# Pop.net
KiCad netlist of a schematic drawn in Altium Designer
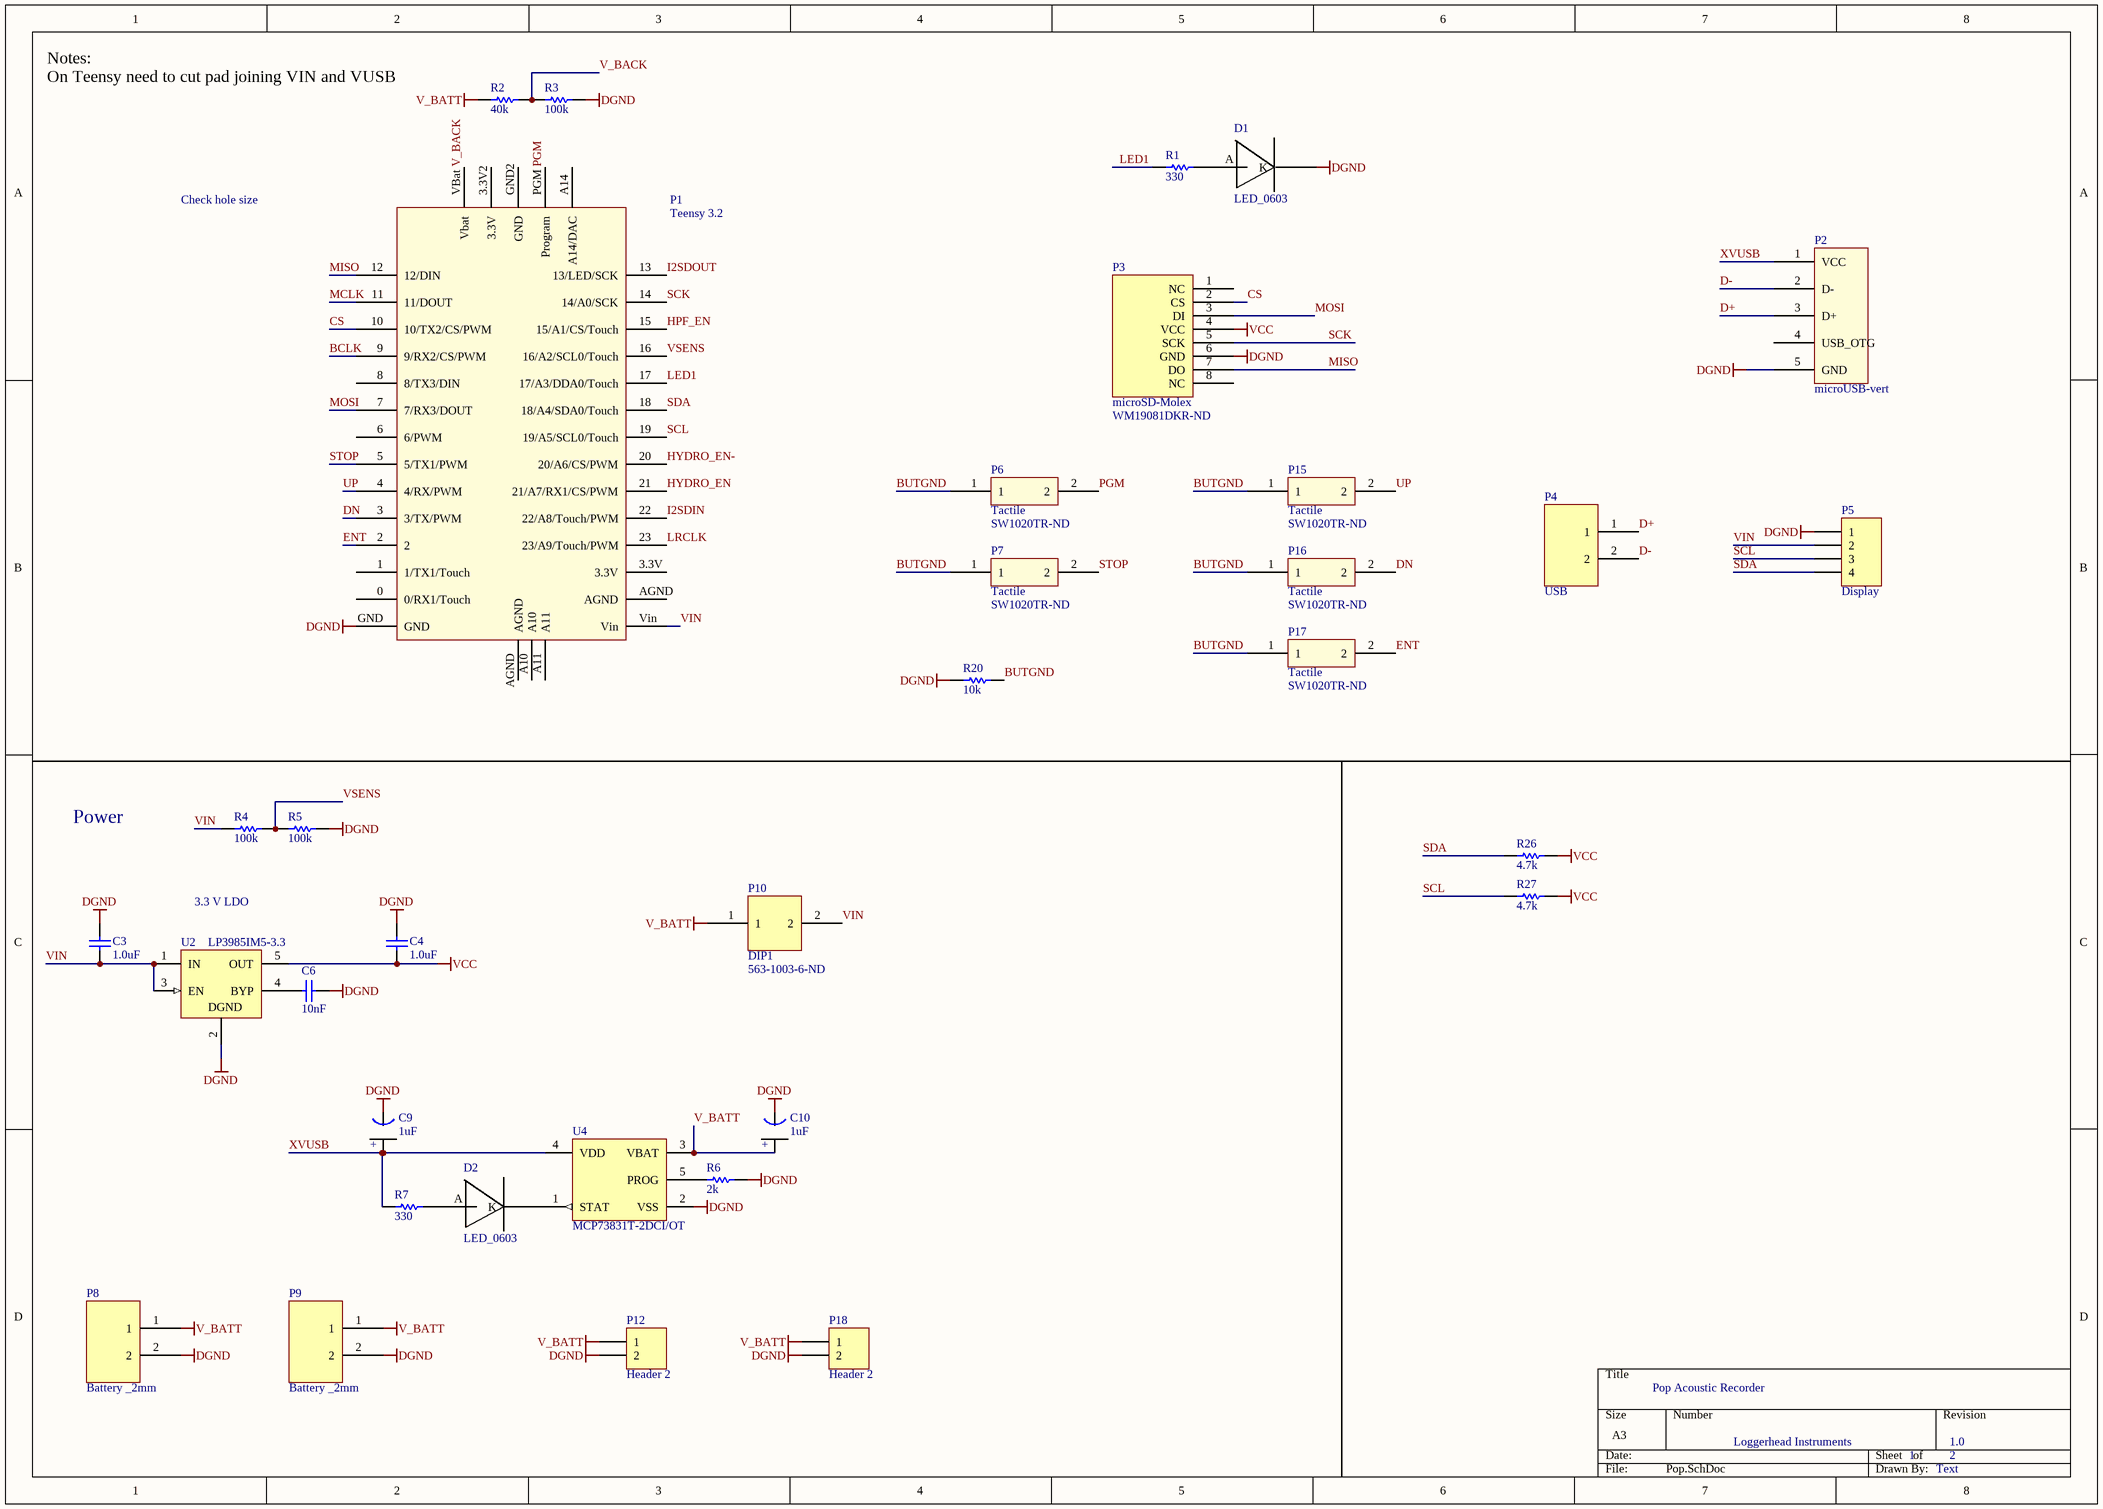
[diagram p0: Pop.SchDoc]

(export (version "E")
  (design (tool "Eeschema 10.0.6"))
  (components
    (comp (ref "C3")
      (value "1.0uF")
      (footprint "0402")
      (description "Ceramic Chip Capacitor - Standard")
      (fields (field (name "PUBLISHER") "Altium Limited"))
      (libsource (lib "KEMET Chip Capacitor") (part "C0402"))
    )
    (comp (ref "C4")
      (value "1.0uF")
      (footprint "0402")
      (description "Ceramic Chip Capacitor - Standard")
      (fields (field (name "PUBLISHER") "Altium Limited"))
      (libsource (lib "KEMET Chip Capacitor") (part "C0402"))
    )
    (comp (ref "C6")
      (value "10nF")
      (footprint "0402")
      (description "Ceramic Chip Capacitor - Standard")
      (fields (field (name "PUBLISHER") "Altium Limited"))
      (libsource (lib "KEMET Chip Capacitor") (part "C0402"))
    )
    (comp (ref "C9") (value "1uF") (footprint "Tant0805") (libsource (lib "Loggerhead") (part "Tant0805")))
    (comp (ref "C10") (value "1uF") (footprint "Tant0805") (libsource (lib "Loggerhead") (part "Tant0805")))
    (comp (ref "D1")
      (value "LED_0603")
      (footprint "Diode0603")
      (libsource (lib "Loggerhead") (part "LED_0603"))
    )
    (comp (ref "D2")
      (value "LED_0603")
      (footprint "Diode0603")
      (libsource (lib "Loggerhead") (part "LED_0603"))
    )
    (comp (ref "P1")
      (value "Teensy 3.2")
      (footprint "Teensy3.x")
      (libsource (lib "Teensy") (part "Teensy3.x"))
    )
    (comp (ref "P2")
      (value "microUSB-vert")
      (footprint "MICROUSB-VERT")
      (description "Molex 105133-0011")
      (libsource (lib "Loggerhead") (part "microUSB-vert"))
    )
    (comp (ref "P3")
      (value "microSD-Molex")
      (footprint "microSD_Molex_hinged")
      (fields (field (name "SUPPLIER PART NUMBER 1") "WM19081DKR-ND"))
      (libsource (lib "Loggerhead") (part "microSD_Molex_hinged"))
    )
    (comp (ref "P4")
      (value "USB")
      (footprint "HDR_2x1_2mm")
      (description "Charging Connector")
      (libsource (lib "Loggerhead") (part "HDR_2x1_2mm"))
    )
    (comp (ref "P5")
      (value "Display")
      (footprint "HDR1X4")
      (description "Header, 4-Pin")
      (fields (field (name "PUBLISHER") "Altium Limited"))
      (libsource (lib "Miscellaneous Connectors") (part "Header 4"))
    )
    (comp (ref "P6")
      (value "Tactile")
      (footprint "Tactile-B3U-1000")
      (fields (field (name "SUPPLIER PART NUMBER 1") "SW1020TR-ND"))
      (libsource (lib "Loggerhead") (part "Tactile_B3U-1000"))
    )
    (comp (ref "P7")
      (value "Tactile")
      (footprint "Tactile-B3U-1000")
      (fields (field (name "SUPPLIER PART NUMBER 1") "SW1020TR-ND"))
      (libsource (lib "Loggerhead") (part "Tactile_B3U-1000"))
    )
    (comp (ref "P8")
      (value "Battery _2mm")
      (footprint "HDR_2x1_2mm")
      (description "Charging Connector")
      (libsource (lib "Loggerhead") (part "HDR_2x1_2mm"))
    )
    (comp (ref "P9")
      (value "Battery _2mm")
      (footprint "HDR_2x1_2mm")
      (description "Charging Connector")
      (libsource (lib "Loggerhead") (part "HDR_2x1_2mm"))
    )
    (comp (ref "P10")
      (value "DIP1")
      (footprint "DIP1")
      (fields (field (name "SUPPLIER PART NUMBER 1") "563-1003-6-ND"))
      (libsource (lib "Loggerhead") (part "DIP1"))
    )
    (comp (ref "P12")
      (value "Header 2")
      (footprint "HDR1X2")
      (description "Header, 2-Pin")
      (fields (field (name "PUBLISHER") "Altium Limited"))
      (libsource (lib "Miscellaneous Connectors") (part "Header 2"))
    )
    (comp (ref "P15")
      (value "Tactile")
      (footprint "Tactile-B3U-1000")
      (fields (field (name "SUPPLIER PART NUMBER 1") "SW1020TR-ND"))
      (libsource (lib "Loggerhead") (part "Tactile_B3U-1000"))
    )
    (comp (ref "P16")
      (value "Tactile")
      (footprint "Tactile-B3U-1000")
      (fields (field (name "SUPPLIER PART NUMBER 1") "SW1020TR-ND"))
      (libsource (lib "Loggerhead") (part "Tactile_B3U-1000"))
    )
    (comp (ref "P17")
      (value "Tactile")
      (footprint "Tactile-B3U-1000")
      (fields (field (name "SUPPLIER PART NUMBER 1") "SW1020TR-ND"))
      (libsource (lib "Loggerhead") (part "Tactile_B3U-1000"))
    )
    (comp (ref "P18")
      (value "Header 2")
      (footprint "HDR1X2")
      (description "Header, 2-Pin")
      (fields (field (name "PUBLISHER") "Altium Limited"))
      (libsource (lib "Miscellaneous Connectors") (part "Header 2"))
    )
    (comp (ref "R1")
      (value "330")
      (footprint "3-0603")
      (fields (field (name "PUBLISHER") "Altium Limited"))
      (libsource (lib "Panasonic Resistor") (part "ERJ3RK"))
    )
    (comp (ref "R2")
      (value "40k")
      (footprint "3-0603")
      (fields (field (name "PUBLISHER") "Altium Limited"))
      (libsource (lib "Panasonic Resistor") (part "ERJ3RK"))
    )
    (comp (ref "R3")
      (value "100k")
      (footprint "3-0603")
      (fields (field (name "PUBLISHER") "Altium Limited"))
      (libsource (lib "Panasonic Resistor") (part "ERJ3RK"))
    )
    (comp (ref "R4")
      (value "100k")
      (footprint "3-0603")
      (fields (field (name "PUBLISHER") "Altium Limited"))
      (libsource (lib "Panasonic Resistor") (part "ERJ3RK"))
    )
    (comp (ref "R5")
      (value "100k")
      (footprint "3-0603")
      (fields (field (name "PUBLISHER") "Altium Limited"))
      (libsource (lib "Panasonic Resistor") (part "ERJ3RK"))
    )
    (comp (ref "R6")
      (value "2k")
      (footprint "3-0603")
      (fields (field (name "PUBLISHER") "Altium Limited"))
      (libsource (lib "Panasonic Resistor") (part "ERJ3RK"))
    )
    (comp (ref "R7")
      (value "330")
      (footprint "3-0603")
      (fields (field (name "PUBLISHER") "Altium Limited"))
      (libsource (lib "Panasonic Resistor") (part "ERJ3RK"))
    )
    (comp (ref "R20")
      (value "10k")
      (footprint "3-0603")
      (fields (field (name "PUBLISHER") "Altium Limited"))
      (libsource (lib "Panasonic Resistor") (part "ERJ3RK"))
    )
    (comp (ref "R26")
      (value "4.7k")
      (footprint "3-0603")
      (fields (field (name "PUBLISHER") "Altium Limited"))
      (libsource (lib "Panasonic Resistor") (part "ERJ3RK"))
    )
    (comp (ref "R27")
      (value "4.7k")
      (footprint "3-0603")
      (fields (field (name "PUBLISHER") "Altium Limited"))
      (libsource (lib "Panasonic Resistor") (part "ERJ3RK"))
    )
    (comp (ref "U2")
      (value "LP3985IM5-3.3")
      (footprint "MF05A_N")
      (description "Micropower, 150mA Low-Noise Ultra Low-Dropout CMOS Voltage Regulator")
      (fields
        (field (name "MANUFACTURER") "National Semiconductor")
        (field (name "DIGIKEYPARTNUMBER") "LP3985IM5-3.3CT-ND")
        (field (name "PUBLISHER") "Altium Limited")
      )
      (libsource (lib "NSC LDO") (part "LP3985IM5-3.3"))
    )
    (comp (ref "U4")
      (value "MCP73831T-2DCI/OT")
      (footprint "SOT-23-OT5_N")
      (libsource (lib "Microchip Power Management Battery Management") (part "MCP73831T-2DCI/OT"))
    )
  )
  (nets
    (net (code "1") (name "/BCLK") (class "Default")
      (node (ref "P1") (pin "9") (pinfunction "9/RX2/CS/PWM_9") (pintype "passive"))
    )
    (net (code "2") (name "/BUTGND") (class "Default")
      (node (ref "P15") (pin "1") (pinfunction "1_1") (pintype "passive"))
      (node (ref "P16") (pin "1") (pinfunction "1_1") (pintype "passive"))
      (node (ref "P17") (pin "1") (pinfunction "1_1") (pintype "passive"))
      (node (ref "P6") (pin "1") (pinfunction "1_1") (pintype "passive"))
      (node (ref "P7") (pin "1") (pinfunction "1_1") (pintype "passive"))
      (node (ref "R20") (pin "1") (pinfunction "1_1") (pintype "passive"))
    )
    (net (code "3") (name "/CS") (class "Default")
      (node (ref "P1") (pin "10") (pinfunction "10/TX2/CS/PWM_10") (pintype "passive"))
      (node (ref "P3") (pin "2") (pinfunction "CS_2") (pintype "passive"))
    )
    (net (code "4") (name "/D+") (class "Default")
      (node (ref "P2") (pin "3") (pinfunction "D+_3") (pintype "passive"))
      (node (ref "P4") (pin "1") (pinfunction "1_1") (pintype "passive"))
    )
    (net (code "5") (name "/D-") (class "Default")
      (node (ref "P2") (pin "2") (pinfunction "D-_2") (pintype "passive"))
      (node (ref "P4") (pin "2") (pinfunction "2_2") (pintype "passive"))
    )
    (net (code "6") (name "/DN") (class "Default")
      (node (ref "P1") (pin "3") (pinfunction "3/TX/PWM_3") (pintype "passive"))
      (node (ref "P16") (pin "2") (pinfunction "2_2") (pintype "passive"))
    )
    (net (code "7") (name "/ENT") (class "Default")
      (node (ref "P1") (pin "2") (pinfunction "2_2") (pintype "passive"))
      (node (ref "P17") (pin "2") (pinfunction "2_2") (pintype "passive"))
    )
    (net (code "8") (name "/HPF_EN") (class "Default")
      (node (ref "P1") (pin "15") (pinfunction "15/A1/CS/Touch_15") (pintype "passive"))
    )
    (net (code "9") (name "/HYDRO_EN") (class "Default")
      (node (ref "P1") (pin "21") (pinfunction "21/A7/RX1/CS/PWM_21") (pintype "passive"))
    )
    (net (code "10") (name "/HYDRO_EN-") (class "Default")
      (node (ref "P1") (pin "20") (pinfunction "20/A6/CS/PWM_20") (pintype "passive"))
    )
    (net (code "11") (name "/I2SDIN") (class "Default")
      (node (ref "P1") (pin "22") (pinfunction "22/A8/Touch/PWM_22") (pintype "passive"))
    )
    (net (code "12") (name "/I2SDOUT") (class "Default")
      (node (ref "P1") (pin "13") (pinfunction "13/LED/SCK_13") (pintype "passive"))
    )
    (net (code "13") (name "/LED1") (class "Default")
      (node (ref "P1") (pin "17") (pinfunction "17/A3/DDA0/Touch_17") (pintype "passive"))
      (node (ref "R1") (pin "1") (pinfunction "1_1") (pintype "passive"))
    )
    (net (code "14") (name "/LRCLK") (class "Default")
      (node (ref "P1") (pin "23") (pinfunction "23/A9/Touch/PWM_23") (pintype "passive"))
    )
    (net (code "15") (name "/MCLK") (class "Default")
      (node (ref "P1") (pin "11") (pinfunction "11/DOUT_11") (pintype "passive"))
    )
    (net (code "16") (name "/MISO") (class "Default")
      (node (ref "P1") (pin "12") (pinfunction "12/DIN_12") (pintype "passive"))
      (node (ref "P3") (pin "7") (pinfunction "DO_7") (pintype "passive"))
    )
    (net (code "17") (name "/MOSI") (class "Default")
      (node (ref "P1") (pin "7") (pinfunction "7/RX3/DOUT_7") (pintype "passive"))
      (node (ref "P3") (pin "3") (pinfunction "DI_3") (pintype "passive"))
    )
    (net (code "18") (name "/PGM") (class "Default")
      (node (ref "P1") (pin "PGM") (pinfunction "Program_PGM") (pintype "passive"))
      (node (ref "P6") (pin "2") (pinfunction "2_2") (pintype "passive"))
    )
    (net (code "19") (name "/SCK") (class "Default")
      (node (ref "P1") (pin "14") (pinfunction "14/A0/SCK_14") (pintype "passive"))
      (node (ref "P3") (pin "5") (pinfunction "SCK_5") (pintype "passive"))
    )
    (net (code "20") (name "/SCL") (class "Default")
      (node (ref "P1") (pin "19") (pinfunction "19/A5/SCL0/Touch_19") (pintype "passive"))
      (node (ref "P5") (pin "3") (pinfunction "3_3") (pintype "passive"))
      (node (ref "R27") (pin "1") (pinfunction "1_1") (pintype "passive"))
    )
    (net (code "21") (name "/SDA") (class "Default")
      (node (ref "P1") (pin "18") (pinfunction "18/A4/SDA0/Touch_18") (pintype "passive"))
      (node (ref "P5") (pin "4") (pinfunction "4_4") (pintype "passive"))
      (node (ref "R26") (pin "2") (pinfunction "2_2") (pintype "passive"))
    )
    (net (code "22") (name "/STOP") (class "Default")
      (node (ref "P1") (pin "5") (pinfunction "5/TX1/PWM_5") (pintype "passive"))
      (node (ref "P7") (pin "2") (pinfunction "2_2") (pintype "passive"))
    )
    (net (code "23") (name "/UP") (class "Default")
      (node (ref "P1") (pin "4") (pinfunction "4/RX/PWM_4") (pintype "passive"))
      (node (ref "P15") (pin "2") (pinfunction "2_2") (pintype "passive"))
    )
    (net (code "24") (name "/VIN") (class "Default")
      (node (ref "C3") (pin "1") (pinfunction "1_1") (pintype "passive"))
      (node (ref "P1") (pin "Vin") (pinfunction "Vin_Vin") (pintype "passive"))
      (node (ref "P10") (pin "2") (pinfunction "2_2") (pintype "passive"))
      (node (ref "P5") (pin "2") (pinfunction "2_2") (pintype "passive"))
      (node (ref "R4") (pin "2") (pinfunction "2_2") (pintype "passive"))
      (node (ref "U2") (pin "1") (pinfunction "IN_1") (pintype "power_in"))
      (node (ref "U2") (pin "3") (pinfunction "EN_3") (pintype "input"))
    )
    (net (code "25") (name "/VSENS") (class "Default")
      (node (ref "P1") (pin "16") (pinfunction "16/A2/SCL0/Touch_16") (pintype "passive"))
      (node (ref "R4") (pin "1") (pinfunction "1_1") (pintype "passive"))
      (node (ref "R5") (pin "2") (pinfunction "2_2") (pintype "passive"))
    )
    (net (code "26") (name "/V_BACK") (class "Default")
      (node (ref "P1") (pin "VBat") (pinfunction "Vbat_VBat") (pintype "passive"))
      (node (ref "R2") (pin "1") (pinfunction "1_1") (pintype "passive"))
      (node (ref "R3") (pin "2") (pinfunction "2_2") (pintype "passive"))
    )
    (net (code "27") (name "/XVUSB") (class "Default")
      (node (ref "C9") (pin "2") (pinfunction "+_2") (pintype "passive"))
      (node (ref "P2") (pin "1") (pinfunction "VCC_1") (pintype "passive"))
      (node (ref "R7") (pin "1") (pinfunction "1_1") (pintype "passive"))
      (node (ref "U4") (pin "4") (pinfunction "VDD_4") (pintype "power_in"))
    )
    (net (code "28") (name "DGND") (class "Default")
      (node (ref "C10") (pin "1") (pinfunction "GND_1") (pintype "passive"))
      (node (ref "C3") (pin "2") (pinfunction "2_2") (pintype "passive"))
      (node (ref "C4") (pin "2") (pinfunction "2_2") (pintype "passive"))
      (node (ref "C6") (pin "1") (pinfunction "1_1") (pintype "passive"))
      (node (ref "C9") (pin "1") (pinfunction "GND_1") (pintype "passive"))
      (node (ref "D1") (pin "K") (pinfunction "K_K") (pintype "passive"))
      (node (ref "P1") (pin "GND") (pinfunction "GND_GND") (pintype "passive"))
      (node (ref "P12") (pin "2") (pinfunction "2_2") (pintype "passive"))
      (node (ref "P18") (pin "2") (pinfunction "2_2") (pintype "passive"))
      (node (ref "P2") (pin "5") (pinfunction "GND_5") (pintype "passive"))
      (node (ref "P3") (pin "6") (pinfunction "GND_6") (pintype "passive"))
      (node (ref "P5") (pin "1") (pinfunction "1_1") (pintype "passive"))
      (node (ref "P8") (pin "2") (pinfunction "2_2") (pintype "passive"))
      (node (ref "P9") (pin "2") (pinfunction "2_2") (pintype "passive"))
      (node (ref "R20") (pin "2") (pinfunction "2_2") (pintype "passive"))
      (node (ref "R3") (pin "1") (pinfunction "1_1") (pintype "passive"))
      (node (ref "R5") (pin "1") (pinfunction "1_1") (pintype "passive"))
      (node (ref "R6") (pin "1") (pinfunction "1_1") (pintype "passive"))
      (node (ref "U2") (pin "2") (pinfunction "GND_2") (pintype "power_in"))
      (node (ref "U4") (pin "2") (pinfunction "VSS_2") (pintype "power_in"))
    )
    (net (code "29") (name "Net-(D1-PadA)") (class "Default")
      (node (ref "D1") (pin "A") (pinfunction "A_A") (pintype "passive"))
      (node (ref "R1") (pin "2") (pinfunction "2_2") (pintype "passive"))
    )
    (net (code "30") (name "Net-(D2-PadA)") (class "Default")
      (node (ref "D2") (pin "A") (pinfunction "A_A") (pintype "passive"))
      (node (ref "R7") (pin "2") (pinfunction "2_2") (pintype "passive"))
    )
    (net (code "31") (name "Net-(U2-BYP)") (class "Default")
      (node (ref "C6") (pin "2") (pinfunction "2_2") (pintype "passive"))
      (node (ref "U2") (pin "4") (pinfunction "BYP_4") (pintype "passive"))
    )
    (net (code "32") (name "Net-(U4-PROG)") (class "Default")
      (node (ref "R6") (pin "2") (pinfunction "2_2") (pintype "passive"))
      (node (ref "U4") (pin "5") (pinfunction "PROG_5") (pintype "passive"))
    )
    (net (code "33") (name "Net-(U4-STAT)") (class "Default")
      (node (ref "D2") (pin "K") (pinfunction "K_K") (pintype "passive"))
      (node (ref "U4") (pin "1") (pinfunction "STAT_1") (pintype "output"))
    )
    (net (code "34") (name "VCC") (class "Default")
      (node (ref "C4") (pin "1") (pinfunction "1_1") (pintype "passive"))
      (node (ref "P3") (pin "4") (pinfunction "VCC_4") (pintype "passive"))
      (node (ref "R26") (pin "1") (pinfunction "1_1") (pintype "passive"))
      (node (ref "R27") (pin "2") (pinfunction "2_2") (pintype "passive"))
      (node (ref "U2") (pin "5") (pinfunction "OUT_5") (pintype "power_in"))
    )
    (net (code "35") (name "V_BATT") (class "Default")
      (node (ref "C10") (pin "2") (pinfunction "+_2") (pintype "passive"))
      (node (ref "P10") (pin "1") (pinfunction "1_1") (pintype "passive"))
      (node (ref "P12") (pin "1") (pinfunction "1_1") (pintype "passive"))
      (node (ref "P18") (pin "1") (pinfunction "1_1") (pintype "passive"))
      (node (ref "P8") (pin "1") (pinfunction "1_1") (pintype "passive"))
      (node (ref "P9") (pin "1") (pinfunction "1_1") (pintype "passive"))
      (node (ref "R2") (pin "2") (pinfunction "2_2") (pintype "passive"))
      (node (ref "U4") (pin "3") (pinfunction "VBAT_3") (pintype "power_in"))
    )
    (net (code "36") (name "unconnected-(P1-0{slash}RX1{slash}Touch-Pad0)") (class "Default")
      (node (ref "P1") (pin "0") (pinfunction "0/RX1/Touch_0") (pintype "passive"))
    )
    (net (code "37") (name "unconnected-(P1-1{slash}TX1{slash}Touch-Pad1)") (class "Default")
      (node (ref "P1") (pin "1") (pinfunction "1/TX1/Touch_1") (pintype "passive"))
    )
    (net (code "38") (name "unconnected-(P1-3.3V-Pad3.3V2)") (class "Default")
      (node (ref "P1") (pin "3.3V2") (pinfunction "3.3V_3.3V2") (pintype "passive"))
    )
    (net (code "39") (name "unconnected-(P1-6{slash}PWM-Pad6)") (class "Default")
      (node (ref "P1") (pin "6") (pinfunction "6/PWM_6") (pintype "passive"))
    )
    (net (code "40") (name "unconnected-(P1-8{slash}TX3{slash}DIN-Pad8)") (class "Default")
      (node (ref "P1") (pin "8") (pinfunction "8/TX3/DIN_8") (pintype "passive"))
    )
    (net (code "41") (name "unconnected-(P1-A14{slash}DAC-PadA14)") (class "Default")
      (node (ref "P1") (pin "A14") (pinfunction "A14/DAC_A14") (pintype "passive"))
    )
    (net (code "42") (name "unconnected-(P1-GND-PadGND2)") (class "Default")
      (node (ref "P1") (pin "GND2") (pinfunction "GND_GND2") (pintype "passive"))
    )
    (net (code "43") (name "unconnected-(P1-Pad3.3V)") (class "Default")
      (node (ref "P1") (pin "3.3V") (pinfunction "3.3V_3.3V") (pintype "passive"))
    )
    (net (code "44") (name "unconnected-(P1-PadA10)") (class "Default")
      (node (ref "P1") (pin "A10") (pinfunction "A10_A10") (pintype "passive"))
    )
    (net (code "45") (name "unconnected-(P1-PadA11)") (class "Default")
      (node (ref "P1") (pin "A11") (pinfunction "A11_A11") (pintype "passive"))
    )
    (net (code "46") (name "unconnected-(P1-PadAGND)") (class "Default")
      (node (ref "P1") (pin "AGND") (pinfunction "AGND_AGND") (pintype "passive"))
    )
    (net (code "47") (name "unconnected-(P1-PadAGND)_1") (class "Default")
      (node (ref "P1") (pin "AGND") (pinfunction "AGND_AGND") (pintype "passive"))
    )
    (net (code "48") (name "unconnected-(P2-USB_OTG-Pad4)") (class "Default")
      (node (ref "P2") (pin "4") (pinfunction "USB_OTG_4") (pintype "passive"))
    )
    (net (code "49") (name "unconnected-(P3-NC-Pad1)") (class "Default")
      (node (ref "P3") (pin "1") (pinfunction "NC_1") (pintype "passive"))
    )
    (net (code "50") (name "unconnected-(P3-NC-Pad8)") (class "Default")
      (node (ref "P3") (pin "8") (pinfunction "NC_8") (pintype "passive"))
    )
  )
)
